# portExpander.net
KiCad netlist of a schematic drawn in Altium Designer
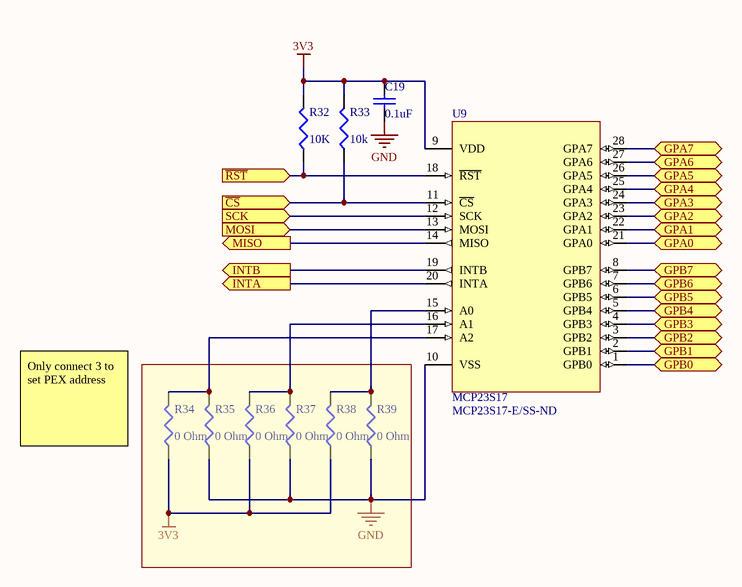
[diagram p0: portExpander.SchDoc]

(export (version "E")
  (design (tool "Eeschema 10.0.6"))
  (components
    (comp (ref "C19")
      (value "0.1uF")
      (footprint "1608[0603]")
      (description "Capacitor (Semiconductor SIM Model)")
      (fields (field (name "PUBLISHER") "Altium Limited"))
      (libsource (lib "Miscellaneous Devices") (part "Cap Semi"))
    )
    (comp (ref "R32")
      (value "10K")
      (footprint "J1-0603")
      (description "Resistor")
      (fields (field (name "PUBLISHER") "Altium Limited"))
      (libsource (lib "Miscellaneous Devices") (part "Res3"))
    )
    (comp (ref "R33")
      (value "10k")
      (footprint "J1-0603")
      (description "Resistor")
      (fields (field (name "PUBLISHER") "Altium Limited"))
      (libsource (lib "Miscellaneous Devices") (part "Res3"))
    )
    (comp (ref "R34")
      (value "0 Ohm")
      (footprint "J1-0603")
      (description "Resistor")
      (fields (field (name "PUBLISHER") "Altium Limited"))
      (libsource (lib "Miscellaneous Devices") (part "Res3"))
    )
    (comp (ref "R35")
      (value "0 Ohm")
      (footprint "J1-0603")
      (description "Resistor")
      (fields (field (name "PUBLISHER") "Altium Limited"))
      (libsource (lib "Miscellaneous Devices") (part "Res3"))
    )
    (comp (ref "R36")
      (value "0 Ohm")
      (footprint "J1-0603")
      (description "Resistor")
      (fields (field (name "PUBLISHER") "Altium Limited"))
      (libsource (lib "Miscellaneous Devices") (part "Res3"))
    )
    (comp (ref "R37")
      (value "0 Ohm")
      (footprint "J1-0603")
      (description "Resistor")
      (fields (field (name "PUBLISHER") "Altium Limited"))
      (libsource (lib "Miscellaneous Devices") (part "Res3"))
    )
    (comp (ref "R38")
      (value "0 Ohm")
      (footprint "J1-0603")
      (description "Resistor")
      (fields (field (name "PUBLISHER") "Altium Limited"))
      (libsource (lib "Miscellaneous Devices") (part "Res3"))
    )
    (comp (ref "R39")
      (value "0 Ohm")
      (footprint "J1-0603")
      (description "Resistor")
      (fields (field (name "PUBLISHER") "Altium Limited"))
      (libsource (lib "Miscellaneous Devices") (part "Res3"))
    )
    (comp (ref "U9")
      (value "MCP23S17")
      (footprint "SOP65P780X200-28N")
      (description "16 bit I/O expander with SPI interface.")
      (fields (field (name "SUPPLIER PART NUMBER 1") "MCP23S17-E/SS-ND"))
      (libsource (lib "ICs") (part "MCP23S17"))
    )
  )
  (nets
    (net (code "1") (name "/GPA0") (class "Default")
      (node (ref "U9") (pin "21") (pinfunction "GPA0_21") (pintype "bidirectional"))
    )
    (net (code "2") (name "/GPA1") (class "Default")
      (node (ref "U9") (pin "22") (pinfunction "GPA1_22") (pintype "bidirectional"))
    )
    (net (code "3") (name "/GPA2") (class "Default")
      (node (ref "U9") (pin "23") (pinfunction "GPA2_23") (pintype "bidirectional"))
    )
    (net (code "4") (name "/GPA3") (class "Default")
      (node (ref "U9") (pin "24") (pinfunction "GPA3_24") (pintype "bidirectional"))
    )
    (net (code "5") (name "/GPA4") (class "Default")
      (node (ref "U9") (pin "25") (pinfunction "GPA4_25") (pintype "bidirectional"))
    )
    (net (code "6") (name "/GPA5") (class "Default")
      (node (ref "U9") (pin "26") (pinfunction "GPA5_26") (pintype "bidirectional"))
    )
    (net (code "7") (name "/GPA6") (class "Default")
      (node (ref "U9") (pin "27") (pinfunction "GPA6_27") (pintype "bidirectional"))
    )
    (net (code "8") (name "/GPA7") (class "Default")
      (node (ref "U9") (pin "28") (pinfunction "GPA7_28") (pintype "bidirectional"))
    )
    (net (code "9") (name "/GPB0") (class "Default")
      (node (ref "U9") (pin "1") (pinfunction "GPB0_1") (pintype "bidirectional"))
    )
    (net (code "10") (name "/GPB1") (class "Default")
      (node (ref "U9") (pin "2") (pinfunction "GPB1_2") (pintype "bidirectional"))
    )
    (net (code "11") (name "/GPB2") (class "Default")
      (node (ref "U9") (pin "3") (pinfunction "GPB2_3") (pintype "bidirectional"))
    )
    (net (code "12") (name "/GPB3") (class "Default")
      (node (ref "U9") (pin "4") (pinfunction "GPB3_4") (pintype "bidirectional"))
    )
    (net (code "13") (name "/GPB4") (class "Default")
      (node (ref "U9") (pin "5") (pinfunction "GPB4_5") (pintype "bidirectional"))
    )
    (net (code "14") (name "/GPB5") (class "Default")
      (node (ref "U9") (pin "6") (pinfunction "GPB5_6") (pintype "bidirectional"))
    )
    (net (code "15") (name "/GPB6") (class "Default")
      (node (ref "U9") (pin "7") (pinfunction "GPB6_7") (pintype "bidirectional"))
    )
    (net (code "16") (name "/GPB7") (class "Default")
      (node (ref "U9") (pin "8") (pinfunction "GPB7_8") (pintype "bidirectional"))
    )
    (net (code "17") (name "/INTA") (class "Default")
      (node (ref "U9") (pin "20") (pinfunction "INTA_20") (pintype "output"))
    )
    (net (code "18") (name "/INTB") (class "Default")
      (node (ref "U9") (pin "19") (pinfunction "INTB_19") (pintype "output"))
    )
    (net (code "19") (name "/MISO") (class "Default")
      (node (ref "U9") (pin "14") (pinfunction "MISO_14") (pintype "output"))
    )
    (net (code "20") (name "/MOSI") (class "Default")
      (node (ref "U9") (pin "13") (pinfunction "MOSI_13") (pintype "input"))
    )
    (net (code "21") (name "/SCK") (class "Default")
      (node (ref "U9") (pin "12") (pinfunction "SCK_12") (pintype "input"))
    )
    (net (code "22") (name "/~{CS}") (class "Default")
      (node (ref "R33") (pin "1") (pinfunction "1_1") (pintype "passive"))
      (node (ref "U9") (pin "11") (pinfunction "~{CS}_11") (pintype "input"))
    )
    (net (code "23") (name "/~{RST}") (class "Default")
      (node (ref "R32") (pin "1") (pinfunction "1_1") (pintype "passive"))
      (node (ref "U9") (pin "18") (pinfunction "~{RST}_18") (pintype "input"))
    )
    (net (code "24") (name "3V3") (class "Default")
      (node (ref "C19") (pin "2") (pinfunction "2_2") (pintype "passive"))
      (node (ref "R32") (pin "2") (pinfunction "2_2") (pintype "passive"))
      (node (ref "R33") (pin "2") (pinfunction "2_2") (pintype "passive"))
      (node (ref "R34") (pin "1") (pinfunction "1_1") (pintype "passive"))
      (node (ref "R36") (pin "1") (pinfunction "1_1") (pintype "passive"))
      (node (ref "R38") (pin "1") (pinfunction "1_1") (pintype "passive"))
      (node (ref "U9") (pin "9") (pinfunction "VDD_9") (pintype "power_in"))
    )
    (net (code "25") (name "GND") (class "Default")
      (node (ref "C19") (pin "1") (pinfunction "1_1") (pintype "passive"))
      (node (ref "R35") (pin "1") (pinfunction "1_1") (pintype "passive"))
      (node (ref "R37") (pin "1") (pinfunction "1_1") (pintype "passive"))
      (node (ref "R39") (pin "1") (pinfunction "1_1") (pintype "passive"))
      (node (ref "U9") (pin "10") (pinfunction "VSS_10") (pintype "power_in"))
    )
    (net (code "26") (name "Net-(U9-A0)") (class "Default")
      (node (ref "R38") (pin "2") (pinfunction "2_2") (pintype "passive"))
      (node (ref "R39") (pin "2") (pinfunction "2_2") (pintype "passive"))
      (node (ref "U9") (pin "15") (pinfunction "A0_15") (pintype "input"))
    )
    (net (code "27") (name "Net-(U9-A1)") (class "Default")
      (node (ref "R36") (pin "2") (pinfunction "2_2") (pintype "passive"))
      (node (ref "R37") (pin "2") (pinfunction "2_2") (pintype "passive"))
      (node (ref "U9") (pin "16") (pinfunction "A1_16") (pintype "input"))
    )
    (net (code "28") (name "Net-(U9-A2)") (class "Default")
      (node (ref "R34") (pin "2") (pinfunction "2_2") (pintype "passive"))
      (node (ref "R35") (pin "2") (pinfunction "2_2") (pintype "passive"))
      (node (ref "U9") (pin "17") (pinfunction "A2_17") (pintype "input"))
    )
  )
)
